# Sheet1.net
KiCad netlist of a schematic drawn in Altium Designer
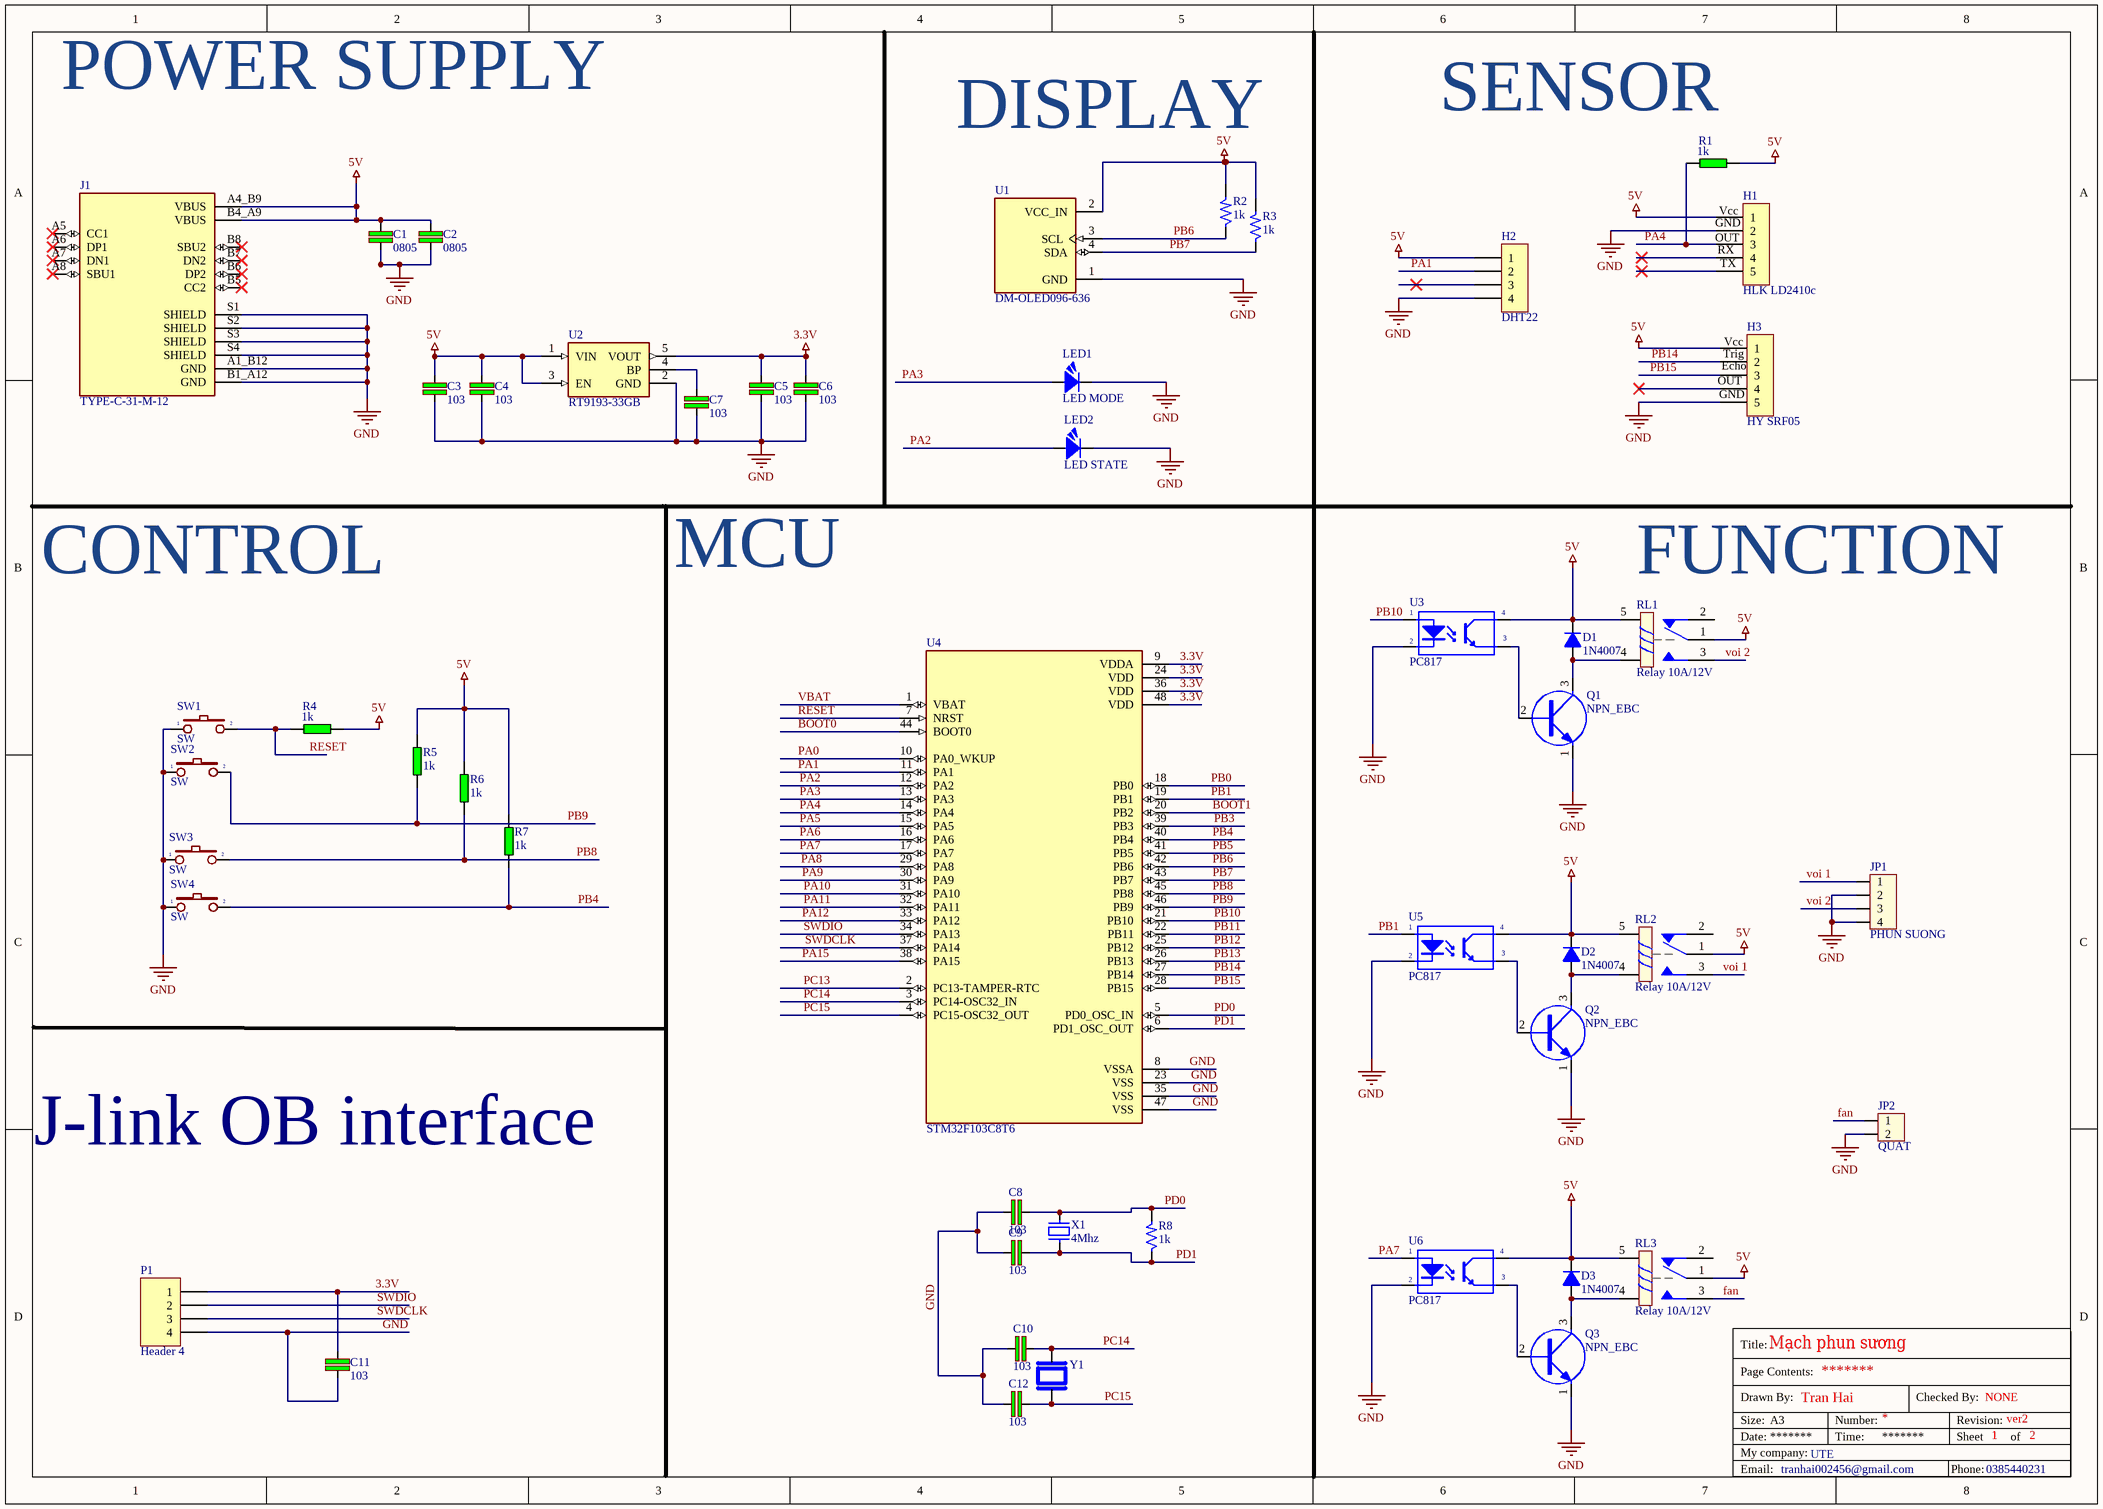
[diagram p0: Sheet1.SchDoc]

(export (version "E")
  (design (tool "Eeschema 10.0.6"))
  (components
    (comp (ref "C1")
      (value "0805")
      (footprint "C-0805")
      (description "Cap SMD")
      (libsource (lib "Library AL") (part "C"))
    )
    (comp (ref "C2")
      (value "0805")
      (footprint "C-0805")
      (description "Cap SMD")
      (libsource (lib "Library AL") (part "C"))
    )
    (comp (ref "C3")
      (value "103")
      (footprint "C-0805")
      (description "Cap SMD")
      (libsource (lib "Library AL") (part "C"))
    )
    (comp (ref "C4")
      (value "103")
      (footprint "C-0805")
      (description "Cap SMD")
      (libsource (lib "Library AL") (part "C"))
    )
    (comp (ref "C5")
      (value "103")
      (footprint "C-0805")
      (description "Cap SMD")
      (libsource (lib "Library AL") (part "C"))
    )
    (comp (ref "C6")
      (value "103")
      (footprint "C-0805")
      (description "Cap SMD")
      (libsource (lib "Library AL") (part "C"))
    )
    (comp (ref "C7")
      (value "103")
      (footprint "C-0805")
      (description "Cap SMD")
      (libsource (lib "Library AL") (part "C"))
    )
    (comp (ref "C8")
      (value "103")
      (footprint "C-0805")
      (description "Cap SMD")
      (libsource (lib "") (part "C_1"))
    )
    (comp (ref "C9")
      (value "103")
      (footprint "C-0805")
      (description "Cap SMD")
      (libsource (lib "") (part "C_1"))
    )
    (comp (ref "C10")
      (value "103")
      (footprint "C-0805")
      (description "Cap SMD")
      (libsource (lib "") (part "C_1"))
    )
    (comp (ref "C11")
      (value "103")
      (footprint "C-0805")
      (description "Cap SMD")
      (libsource (lib "Library AL") (part "C"))
    )
    (comp (ref "C12")
      (value "103")
      (footprint "C-0805")
      (description "Cap SMD")
      (libsource (lib "") (part "C_1"))
    )
    (comp (ref "D1")
      (value "1N4007")
      (footprint "D1A")
      (description "Diode 1A")
      (libsource (lib "Library AL") (part "D1A"))
    )
    (comp (ref "D2")
      (value "1N4007")
      (footprint "D1A")
      (description "Diode 1A")
      (libsource (lib "Library AL") (part "D1A"))
    )
    (comp (ref "D3")
      (value "1N4007")
      (footprint "D1A")
      (description "Diode 1A")
      (libsource (lib "Library AL") (part "D1A"))
    )
    (comp (ref "H1")
      (value "HLK LD2410c")
      (footprint "Header 5P DC 2.54")
      (description "Cắm")
      (libsource (lib "Altium_Lib_by_KhueNguyenCreator") (part "Header 5P 2.54 Duc Cong"))
    )
    (comp (ref "H2")
      (value "DHT22")
      (footprint "XH2.54M-4")
      (description "Cắm")
      (libsource (lib "Altium_Lib_by_KhueNguyenCreator") (part "Header 4P 2.54 Duc Thang"))
    )
    (comp (ref "H3")
      (value "HY SRF05")
      (footprint "XH2.54M-5")
      (description "Cắm")
      (libsource (lib "Altium_Lib_by_KhueNguyenCreator") (part "Header 5P 2.54 Duc Thang"))
    )
    (comp (ref "J1")
      (value "TYPE-C-31-M-12")
      (footprint "HRO_TYPE-C-31-M-12")
      (description "USB Connectors 24 Receptacle 1 8.94*7.3mm RoHS")
      (fields (field (name "MF") "HRO Electronics Co., Ltd."))
      (libsource (lib "TYPE-C-31-M-12") (part "TYPE-C-31-M-12"))
    )
    (comp (ref "JP1")
      (value "PHUN SUONG")
      (footprint "CON4")
      (description "Connector 4")
      (libsource (lib "Library AL") (part "Con4"))
    )
    (comp (ref "JP2")
      (value "QUAT")
      (footprint "CON2")
      (description "Connector 2")
      (libsource (lib "Library AL") (part "Con2"))
    )
    (comp (ref "LED1")
      (value "LED MODE")
      (footprint "LED-3")
      (description "LED Single colour Green and Red")
      (libsource (lib "Library AL") (part "LED_THU"))
    )
    (comp (ref "LED2")
      (value "LED STATE")
      (footprint "LED-3")
      (description "LED Single colour Green and Red")
      (libsource (lib "Library AL") (part "LED_THU"))
    )
    (comp (ref "P1")
      (value "Header 4")
      (footprint "HDR1X4")
      (description "Header, 4-Pin")
      (fields (field (name "PUBLISHER") "Altium Limited"))
      (libsource (lib "Library AL") (part "Header 4"))
    )
    (comp (ref "Q1")
      (value "NPN_EBC")
      (footprint "QTO-92")
      (description "NPN Transistor")
      (libsource (lib "Library AL") (part "NPN_EBC"))
    )
    (comp (ref "Q2")
      (value "NPN_EBC")
      (footprint "QTO-92")
      (description "NPN Transistor")
      (libsource (lib "Library AL") (part "NPN_EBC"))
    )
    (comp (ref "Q3")
      (value "NPN_EBC")
      (footprint "QTO-92")
      (description "NPN Transistor")
      (libsource (lib "Library AL") (part "NPN_EBC"))
    )
    (comp (ref "R1")
      (value "1k")
      (footprint "SM-1206")
      (description "Resistor 1/4W")
      (libsource (lib "") (part "RES_1"))
    )
    (comp (ref "R2")
      (value "1k")
      (footprint "SM-1206")
      (description "Resistor 1/4W")
      (libsource (lib "Library AL") (part "R"))
    )
    (comp (ref "R3")
      (value "1k")
      (footprint "SM-1206")
      (description "Resistor 1/4W")
      (libsource (lib "Library AL") (part "R"))
    )
    (comp (ref "R4")
      (value "1k")
      (footprint "SM-1206")
      (description "Resistor 1/4W")
      (libsource (lib "") (part "RES_1"))
    )
    (comp (ref "R5")
      (value "1k")
      (footprint "SM-1206")
      (description "Resistor 1/4W")
      (libsource (lib "Library AL") (part "RES"))
    )
    (comp (ref "R6")
      (value "1k")
      (footprint "SM-1206")
      (description "Resistor 1/4W")
      (libsource (lib "Library AL") (part "RES"))
    )
    (comp (ref "R7")
      (value "1k")
      (footprint "SM-1206")
      (description "Resistor 1/4W")
      (libsource (lib "Library AL") (part "RES"))
    )
    (comp (ref "R8")
      (value "1k")
      (footprint "SM-1206")
      (description "Resistor 1/4W")
      (libsource (lib "Library AL") (part "R"))
    )
    (comp (ref "RL1")
      (value "Relay 10A/12V")
      (footprint "RL_SPDT_10A")
      (description "Relay SPDT,10A - 12VDC 5 Pin")
      (libsource (lib "syhaunguyen") (part "Relay 1"))
    )
    (comp (ref "RL2")
      (value "Relay 10A/12V")
      (footprint "RL_SPDT_10A")
      (description "Relay SPDT,10A - 12VDC 5 Pin")
      (libsource (lib "syhaunguyen") (part "Relay 1"))
    )
    (comp (ref "RL3")
      (value "Relay 10A/12V")
      (footprint "RL_SPDT_10A")
      (description "Relay SPDT,10A - 12VDC 5 Pin")
      (libsource (lib "syhaunguyen") (part "Relay 1"))
    )
    (comp (ref "SW1")
      (value "SW")
      (footprint "SW2")
      (description "Switch button 2 pin")
      (libsource (lib "Library AL") (part "SW2"))
    )
    (comp (ref "SW2")
      (value "SW")
      (footprint "SW2")
      (description "Switch button 2 pin")
      (libsource (lib "Library AL") (part "SW2"))
    )
    (comp (ref "SW3")
      (value "SW")
      (footprint "SW2")
      (description "Switch button 2 pin")
      (libsource (lib "Library AL") (part "SW2"))
    )
    (comp (ref "SW4")
      (value "SW")
      (footprint "SW2")
      (description "Switch button 2 pin")
      (libsource (lib "Library AL") (part "SW2"))
    )
    (comp (ref "U1")
      (value "DM-OLED096-636")
      (footprint "MODULE_DM-OLED096-636")
      (description "0.96â€ 128 X 64 MONOCHROME GRAPHIC OLED DISPLAY MODULE - I2C")
      (fields (field (name "MF") "Display Module"))
      (libsource (lib "DM-OLED096-636") (part "DM-OLED096-636"))
    )
    (comp (ref "U2")
      (value "RT9193-33GB")
      (footprint "SOT94P279X129-5N")
      (description "Linear Voltage Regulator IC Positive Fixed 1 Output 300mA TSOT-23-5")
      (fields (field (name "MF") "Richtek USA") (field (name "DIGI-KEY_PART_NUMBER") "1028-1014-2-ND"))
      (libsource (lib "RT9193-33GB") (part "RT9193-33GB"))
    )
    (comp (ref "U3")
      (value "PC817")
      (footprint "DIP4/W0.3")
      (description "Single Opto")
      (libsource (lib "syhaunguyen") (part "PC817"))
    )
    (comp (ref "U4")
      (value "STM32F103C8T6")
      (footprint "QFP50P900X900X160-48N")
      (description "ARM® Cortex®-M3 STM32F1 Microcontroller IC 32-Bit 72MHz 64KB (64K x 8) FLASH 48-LQFP (7x7)")
      (fields (field (name "MF") "STMicroelectronics"))
      (libsource (lib "STM32F103C8T6") (part "STM32F103C8T6"))
    )
    (comp (ref "U5")
      (value "PC817")
      (footprint "DIP4/W0.3")
      (description "Single Opto")
      (libsource (lib "syhaunguyen") (part "PC817"))
    )
    (comp (ref "U6")
      (value "PC817")
      (footprint "DIP4/W0.3")
      (description "Single Opto")
      (libsource (lib "syhaunguyen") (part "PC817"))
    )
    (comp (ref "X1")
      (value "4Mhz")
      (footprint "XT2")
      (description "Crystal For all Crystal 2pin.")
      (libsource (lib "syhaunguyen") (part "XT2"))
    )
    (comp (ref "Y1")
      (value "ABS07-32.768KHZ-T")
      (footprint "XTAL_ABS07-32.768KHZ-T")
      (description "32.768 kHz Â±20ppm Crystal 12.5pF 70 kOhms 2-SMD, No Lead")
      (fields (field (name "MF") "Abracon"))
      (libsource (lib "ABS07-32.768KHZ-T") (part "ABS07-32.768KHZ-T"))
    )
  )
  (nets
    (net (code "1") (name "/BOOT0") (class "Default")
      (node (ref "U4") (pin "44") (pinfunction "BOOT0_44") (pintype "input"))
    )
    (net (code "2") (name "/BOOT1") (class "Default")
      (node (ref "U4") (pin "20") (pinfunction "PB2_20") (pintype "bidirectional"))
    )
    (net (code "3") (name "/PA0") (class "Default")
      (node (ref "U4") (pin "10") (pinfunction "PA0_WKUP_10") (pintype "bidirectional"))
    )
    (net (code "4") (name "/PA1") (class "Default")
      (node (ref "H2") (pin "2") (pinfunction "2_2") (pintype "passive"))
      (node (ref "U4") (pin "11") (pinfunction "PA1_11") (pintype "bidirectional"))
    )
    (net (code "5") (name "/PA2") (class "Default")
      (node (ref "LED2") (pin "1") (pinfunction "1_1") (pintype "passive"))
      (node (ref "U4") (pin "12") (pinfunction "PA2_12") (pintype "bidirectional"))
    )
    (net (code "6") (name "/PA3") (class "Default")
      (node (ref "LED1") (pin "1") (pinfunction "1_1") (pintype "passive"))
      (node (ref "U4") (pin "13") (pinfunction "PA3_13") (pintype "bidirectional"))
    )
    (net (code "7") (name "/PA4") (class "Default")
      (node (ref "H1") (pin "3") (pinfunction "3_3") (pintype "passive"))
      (node (ref "R1") (pin "1") (pinfunction "1_1") (pintype "passive"))
      (node (ref "U4") (pin "14") (pinfunction "PA4_14") (pintype "bidirectional"))
    )
    (net (code "8") (name "/PA5") (class "Default")
      (node (ref "U4") (pin "15") (pinfunction "PA5_15") (pintype "bidirectional"))
    )
    (net (code "9") (name "/PA6") (class "Default")
      (node (ref "U4") (pin "16") (pinfunction "PA6_16") (pintype "bidirectional"))
    )
    (net (code "10") (name "/PA7") (class "Default")
      (node (ref "U4") (pin "17") (pinfunction "PA7_17") (pintype "bidirectional"))
      (node (ref "U6") (pin "1") (pinfunction "A_1") (pintype "passive"))
    )
    (net (code "11") (name "/PA8") (class "Default")
      (node (ref "U4") (pin "29") (pinfunction "PA8_29") (pintype "bidirectional"))
    )
    (net (code "12") (name "/PA9") (class "Default")
      (node (ref "U4") (pin "30") (pinfunction "PA9_30") (pintype "bidirectional"))
    )
    (net (code "13") (name "/PA10") (class "Default")
      (node (ref "U4") (pin "31") (pinfunction "PA10_31") (pintype "bidirectional"))
    )
    (net (code "14") (name "/PA11") (class "Default")
      (node (ref "U4") (pin "32") (pinfunction "PA11_32") (pintype "bidirectional"))
    )
    (net (code "15") (name "/PA12") (class "Default")
      (node (ref "U4") (pin "33") (pinfunction "PA12_33") (pintype "bidirectional"))
    )
    (net (code "16") (name "/PA15") (class "Default")
      (node (ref "U4") (pin "38") (pinfunction "PA15_38") (pintype "bidirectional"))
    )
    (net (code "17") (name "/PB0") (class "Default")
      (node (ref "U4") (pin "18") (pinfunction "PB0_18") (pintype "bidirectional"))
    )
    (net (code "18") (name "/PB1") (class "Default")
      (node (ref "U4") (pin "19") (pinfunction "PB1_19") (pintype "bidirectional"))
      (node (ref "U5") (pin "1") (pinfunction "A_1") (pintype "passive"))
    )
    (net (code "19") (name "/PB3") (class "Default")
      (node (ref "U4") (pin "39") (pinfunction "PB3_39") (pintype "bidirectional"))
    )
    (net (code "20") (name "/PB4") (class "Default")
      (node (ref "R7") (pin "1") (pinfunction "1_1") (pintype "passive"))
      (node (ref "SW4") (pin "2") (pinfunction "2_2") (pintype "passive"))
      (node (ref "U4") (pin "40") (pinfunction "PB4_40") (pintype "bidirectional"))
    )
    (net (code "21") (name "/PB5") (class "Default")
      (node (ref "U4") (pin "41") (pinfunction "PB5_41") (pintype "bidirectional"))
    )
    (net (code "22") (name "/PB6") (class "Default")
      (node (ref "R2") (pin "1") (pinfunction "1_1") (pintype "passive"))
      (node (ref "U1") (pin "3") (pinfunction "SCL_3") (pintype "input"))
      (node (ref "U4") (pin "42") (pinfunction "PB6_42") (pintype "bidirectional"))
    )
    (net (code "23") (name "/PB7") (class "Default")
      (node (ref "R3") (pin "1") (pinfunction "1_1") (pintype "passive"))
      (node (ref "U1") (pin "4") (pinfunction "SDA_4") (pintype "bidirectional"))
      (node (ref "U4") (pin "43") (pinfunction "PB7_43") (pintype "bidirectional"))
    )
    (net (code "24") (name "/PB8") (class "Default")
      (node (ref "R6") (pin "1") (pinfunction "1_1") (pintype "passive"))
      (node (ref "SW3") (pin "2") (pinfunction "2_2") (pintype "passive"))
      (node (ref "U4") (pin "45") (pinfunction "PB8_45") (pintype "bidirectional"))
    )
    (net (code "25") (name "/PB9") (class "Default")
      (node (ref "R5") (pin "1") (pinfunction "1_1") (pintype "passive"))
      (node (ref "SW2") (pin "2") (pinfunction "2_2") (pintype "passive"))
      (node (ref "U4") (pin "46") (pinfunction "PB9_46") (pintype "bidirectional"))
    )
    (net (code "26") (name "/PB10") (class "Default")
      (node (ref "U3") (pin "1") (pinfunction "A_1") (pintype "passive"))
      (node (ref "U4") (pin "21") (pinfunction "PB10_21") (pintype "bidirectional"))
    )
    (net (code "27") (name "/PB11") (class "Default")
      (node (ref "U4") (pin "22") (pinfunction "PB11_22") (pintype "bidirectional"))
    )
    (net (code "28") (name "/PB12") (class "Default")
      (node (ref "U4") (pin "25") (pinfunction "PB12_25") (pintype "bidirectional"))
    )
    (net (code "29") (name "/PB13") (class "Default")
      (node (ref "U4") (pin "26") (pinfunction "PB13_26") (pintype "bidirectional"))
    )
    (net (code "30") (name "/PB14") (class "Default")
      (node (ref "H3") (pin "2") (pinfunction "2_2") (pintype "passive"))
      (node (ref "U4") (pin "27") (pinfunction "PB14_27") (pintype "bidirectional"))
    )
    (net (code "31") (name "/PB15") (class "Default")
      (node (ref "H3") (pin "3") (pinfunction "3_3") (pintype "passive"))
      (node (ref "U4") (pin "28") (pinfunction "PB15_28") (pintype "bidirectional"))
    )
    (net (code "32") (name "/PC13") (class "Default")
      (node (ref "U4") (pin "2") (pinfunction "PC13-TAMPER-RTC_2") (pintype "bidirectional"))
    )
    (net (code "33") (name "/PC14") (class "Default")
      (node (ref "C10") (pin "2") (pinfunction "2_2") (pintype "passive"))
      (node (ref "U4") (pin "3") (pinfunction "PC14-OSC32_IN_3") (pintype "bidirectional"))
      (node (ref "Y1") (pin "2") (pinfunction "2_2") (pintype "passive"))
    )
    (net (code "34") (name "/PC15") (class "Default")
      (node (ref "C12") (pin "2") (pinfunction "2_2") (pintype "passive"))
      (node (ref "U4") (pin "4") (pinfunction "PC15-OSC32_OUT_4") (pintype "bidirectional"))
      (node (ref "Y1") (pin "1") (pinfunction "1_1") (pintype "passive"))
    )
    (net (code "35") (name "/PD0") (class "Default")
      (node (ref "C8") (pin "2") (pinfunction "2_2") (pintype "passive"))
      (node (ref "R8") (pin "2") (pinfunction "2_2") (pintype "passive"))
      (node (ref "U4") (pin "5") (pinfunction "PD0_OSC_IN_5") (pintype "bidirectional"))
      (node (ref "X1") (pin "1") (pinfunction "1_1") (pintype "passive"))
    )
    (net (code "36") (name "/PD1") (class "Default")
      (node (ref "C9") (pin "2") (pinfunction "2_2") (pintype "passive"))
      (node (ref "R8") (pin "1") (pinfunction "1_1") (pintype "passive"))
      (node (ref "U4") (pin "6") (pinfunction "PD1_OSC_OUT_6") (pintype "bidirectional"))
      (node (ref "X1") (pin "2") (pinfunction "2_2") (pintype "passive"))
    )
    (net (code "37") (name "/RESET") (class "Default")
      (node (ref "R4") (pin "1") (pinfunction "1_1") (pintype "passive"))
      (node (ref "SW1") (pin "2") (pinfunction "2_2") (pintype "passive"))
      (node (ref "U4") (pin "7") (pinfunction "NRST_7") (pintype "input"))
    )
    (net (code "38") (name "/SWDCLK") (class "Default")
      (node (ref "P1") (pin "3") (pinfunction "3_3") (pintype "passive"))
      (node (ref "U4") (pin "37") (pinfunction "PA14_37") (pintype "bidirectional"))
    )
    (net (code "39") (name "/SWDIO") (class "Default")
      (node (ref "P1") (pin "2") (pinfunction "2_2") (pintype "passive"))
      (node (ref "U4") (pin "34") (pinfunction "PA13_34") (pintype "bidirectional"))
    )
    (net (code "40") (name "/VBAT") (class "Default")
      (node (ref "U4") (pin "1") (pinfunction "VBAT_1") (pintype "bidirectional"))
    )
    (net (code "41") (name "/fan") (class "Default")
      (node (ref "JP2") (pin "1") (pinfunction "1_1") (pintype "passive"))
      (node (ref "RL3") (pin "3") (pinfunction "3_3") (pintype "passive"))
    )
    (net (code "42") (name "/voi 1") (class "Default")
      (node (ref "JP1") (pin "1") (pinfunction "1_1") (pintype "passive"))
      (node (ref "RL2") (pin "3") (pinfunction "3_3") (pintype "passive"))
    )
    (net (code "43") (name "/voi 2") (class "Default")
      (node (ref "JP1") (pin "3") (pinfunction "3_3") (pintype "passive"))
      (node (ref "RL1") (pin "3") (pinfunction "3_3") (pintype "passive"))
    )
    (net (code "44") (name "3.3V") (class "Default")
      (node (ref "C11") (pin "2") (pinfunction "2_2") (pintype "passive"))
      (node (ref "C5") (pin "2") (pinfunction "2_2") (pintype "passive"))
      (node (ref "C6") (pin "2") (pinfunction "2_2") (pintype "passive"))
      (node (ref "P1") (pin "1") (pinfunction "1_1") (pintype "passive"))
      (node (ref "U2") (pin "5") (pinfunction "VOUT_5") (pintype "output"))
      (node (ref "U4") (pin "24") (pinfunction "VDD_24") (pintype "power_in"))
      (node (ref "U4") (pin "36") (pinfunction "VDD_36") (pintype "power_in"))
      (node (ref "U4") (pin "48") (pinfunction "VDD_48") (pintype "power_in"))
      (node (ref "U4") (pin "9") (pinfunction "VDDA_9") (pintype "power_in"))
    )
    (net (code "45") (name "5V") (class "Default")
      (node (ref "C1") (pin "2") (pinfunction "2_2") (pintype "passive"))
      (node (ref "C2") (pin "2") (pinfunction "2_2") (pintype "passive"))
      (node (ref "C3") (pin "2") (pinfunction "2_2") (pintype "passive"))
      (node (ref "C4") (pin "2") (pinfunction "2_2") (pintype "passive"))
      (node (ref "D1") (pin "2") (pinfunction "K_2") (pintype "passive"))
      (node (ref "D2") (pin "2") (pinfunction "K_2") (pintype "passive"))
      (node (ref "D3") (pin "2") (pinfunction "K_2") (pintype "passive"))
      (node (ref "H1") (pin "1") (pinfunction "1_1") (pintype "passive"))
      (node (ref "H2") (pin "1") (pinfunction "1_1") (pintype "passive"))
      (node (ref "H3") (pin "1") (pinfunction "1_1") (pintype "passive"))
      (node (ref "J1") (pin "A4_B9") (pinfunction "VBUS_A4_B9") (pintype "power_in"))
      (node (ref "J1") (pin "B4_A9") (pinfunction "VBUS_B4_A9") (pintype "power_in"))
      (node (ref "R1") (pin "2") (pinfunction "2_2") (pintype "passive"))
      (node (ref "R2") (pin "2") (pinfunction "2_2") (pintype "passive"))
      (node (ref "R3") (pin "2") (pinfunction "2_2") (pintype "passive"))
      (node (ref "R4") (pin "2") (pinfunction "2_2") (pintype "passive"))
      (node (ref "R5") (pin "2") (pinfunction "2_2") (pintype "passive"))
      (node (ref "R6") (pin "2") (pinfunction "2_2") (pintype "passive"))
      (node (ref "R7") (pin "2") (pinfunction "2_2") (pintype "passive"))
      (node (ref "RL1") (pin "1") (pinfunction "1_1") (pintype "passive"))
      (node (ref "RL1") (pin "5") (pinfunction "5_5") (pintype "passive"))
      (node (ref "RL2") (pin "1") (pinfunction "1_1") (pintype "passive"))
      (node (ref "RL2") (pin "5") (pinfunction "5_5") (pintype "passive"))
      (node (ref "RL3") (pin "1") (pinfunction "1_1") (pintype "passive"))
      (node (ref "RL3") (pin "5") (pinfunction "5_5") (pintype "passive"))
      (node (ref "U1") (pin "2") (pinfunction "VCC_IN_2") (pintype "power_in"))
      (node (ref "U2") (pin "1") (pinfunction "VIN_1") (pintype "input"))
      (node (ref "U2") (pin "3") (pinfunction "EN_3") (pintype "input"))
      (node (ref "U3") (pin "4") (pinfunction "C_4") (pintype "passive"))
      (node (ref "U5") (pin "4") (pinfunction "C_4") (pintype "passive"))
      (node (ref "U6") (pin "4") (pinfunction "C_4") (pintype "passive"))
    )
    (net (code "46") (name "GND") (class "Default")
      (node (ref "C1") (pin "1") (pinfunction "1_1") (pintype "passive"))
      (node (ref "C10") (pin "1") (pinfunction "1_1") (pintype "passive"))
      (node (ref "C11") (pin "1") (pinfunction "1_1") (pintype "passive"))
      (node (ref "C12") (pin "1") (pinfunction "1_1") (pintype "passive"))
      (node (ref "C2") (pin "1") (pinfunction "1_1") (pintype "passive"))
      (node (ref "C3") (pin "1") (pinfunction "1_1") (pintype "passive"))
      (node (ref "C4") (pin "1") (pinfunction "1_1") (pintype "passive"))
      (node (ref "C5") (pin "1") (pinfunction "1_1") (pintype "passive"))
      (node (ref "C6") (pin "1") (pinfunction "1_1") (pintype "passive"))
      (node (ref "C7") (pin "1") (pinfunction "1_1") (pintype "passive"))
      (node (ref "C8") (pin "1") (pinfunction "1_1") (pintype "passive"))
      (node (ref "C9") (pin "1") (pinfunction "1_1") (pintype "passive"))
      (node (ref "H1") (pin "2") (pinfunction "2_2") (pintype "passive"))
      (node (ref "H2") (pin "4") (pinfunction "4_4") (pintype "passive"))
      (node (ref "H3") (pin "5") (pinfunction "5_5") (pintype "passive"))
      (node (ref "J1") (pin "A1_B12") (pinfunction "GND_A1_B12") (pintype "power_in"))
      (node (ref "J1") (pin "B1_A12") (pinfunction "GND_B1_A12") (pintype "power_in"))
      (node (ref "J1") (pin "S1") (pinfunction "SHIELD_S1") (pintype "passive"))
      (node (ref "J1") (pin "S2") (pinfunction "SHIELD_S2") (pintype "passive"))
      (node (ref "J1") (pin "S3") (pinfunction "SHIELD_S3") (pintype "passive"))
      (node (ref "J1") (pin "S4") (pinfunction "SHIELD_S4") (pintype "passive"))
      (node (ref "JP1") (pin "2") (pinfunction "2_2") (pintype "passive"))
      (node (ref "JP1") (pin "4") (pinfunction "4_4") (pintype "passive"))
      (node (ref "JP2") (pin "2") (pinfunction "2_2") (pintype "passive"))
      (node (ref "LED1") (pin "2") (pinfunction "2_2") (pintype "passive"))
      (node (ref "LED2") (pin "2") (pinfunction "2_2") (pintype "passive"))
      (node (ref "P1") (pin "4") (pinfunction "4_4") (pintype "passive"))
      (node (ref "Q1") (pin "1") (pinfunction "E_1") (pintype "passive"))
      (node (ref "Q2") (pin "1") (pinfunction "E_1") (pintype "passive"))
      (node (ref "Q3") (pin "1") (pinfunction "E_1") (pintype "passive"))
      (node (ref "SW1") (pin "1") (pinfunction "1_1") (pintype "passive"))
      (node (ref "SW2") (pin "1") (pinfunction "1_1") (pintype "passive"))
      (node (ref "SW3") (pin "1") (pinfunction "1_1") (pintype "passive"))
      (node (ref "SW4") (pin "1") (pinfunction "1_1") (pintype "passive"))
      (node (ref "U1") (pin "1") (pinfunction "GND_1") (pintype "power_in"))
      (node (ref "U2") (pin "2") (pinfunction "GND_2") (pintype "power_in"))
      (node (ref "U3") (pin "2") (pinfunction "K_2") (pintype "passive"))
      (node (ref "U4") (pin "23") (pinfunction "VSS_23") (pintype "power_in"))
      (node (ref "U4") (pin "35") (pinfunction "VSS_35") (pintype "power_in"))
      (node (ref "U4") (pin "47") (pinfunction "VSS_47") (pintype "power_in"))
      (node (ref "U4") (pin "8") (pinfunction "VSSA_8") (pintype "power_in"))
      (node (ref "U5") (pin "2") (pinfunction "K_2") (pintype "passive"))
      (node (ref "U6") (pin "2") (pinfunction "K_2") (pintype "passive"))
    )
    (net (code "47") (name "Net-(D1-A)") (class "Default")
      (node (ref "D1") (pin "1") (pinfunction "A_1") (pintype "passive"))
      (node (ref "Q1") (pin "3") (pinfunction "C_3") (pintype "passive"))
      (node (ref "RL1") (pin "4") (pinfunction "4_4") (pintype "passive"))
    )
    (net (code "48") (name "Net-(D2-A)") (class "Default")
      (node (ref "D2") (pin "1") (pinfunction "A_1") (pintype "passive"))
      (node (ref "Q2") (pin "3") (pinfunction "C_3") (pintype "passive"))
      (node (ref "RL2") (pin "4") (pinfunction "4_4") (pintype "passive"))
    )
    (net (code "49") (name "Net-(D3-A)") (class "Default")
      (node (ref "D3") (pin "1") (pinfunction "A_1") (pintype "passive"))
      (node (ref "Q3") (pin "3") (pinfunction "C_3") (pintype "passive"))
      (node (ref "RL3") (pin "4") (pinfunction "4_4") (pintype "passive"))
    )
    (net (code "50") (name "Net-(Q1-B)") (class "Default")
      (node (ref "Q1") (pin "2") (pinfunction "B_2") (pintype "passive"))
      (node (ref "U3") (pin "3") (pinfunction "E_3") (pintype "passive"))
    )
    (net (code "51") (name "Net-(Q2-B)") (class "Default")
      (node (ref "Q2") (pin "2") (pinfunction "B_2") (pintype "passive"))
      (node (ref "U5") (pin "3") (pinfunction "E_3") (pintype "passive"))
    )
    (net (code "52") (name "Net-(Q3-B)") (class "Default")
      (node (ref "Q3") (pin "2") (pinfunction "B_2") (pintype "passive"))
      (node (ref "U6") (pin "3") (pinfunction "E_3") (pintype "passive"))
    )
    (net (code "53") (name "Net-(U2-BP)") (class "Default")
      (node (ref "C7") (pin "2") (pinfunction "2_2") (pintype "passive"))
      (node (ref "U2") (pin "4") (pinfunction "BP_4") (pintype "passive"))
    )
    (net (code "54") (name "unconnected-(H1-Pad4)") (class "Default")
      (node (ref "H1") (pin "4") (pinfunction "4_4") (pintype "passive"))
    )
    (net (code "55") (name "unconnected-(H1-Pad5)") (class "Default")
      (node (ref "H1") (pin "5") (pinfunction "5_5") (pintype "passive"))
    )
    (net (code "56") (name "unconnected-(H2-Pad3)") (class "Default")
      (node (ref "H2") (pin "3") (pinfunction "3_3") (pintype "passive"))
    )
    (net (code "57") (name "unconnected-(H3-Pad4)") (class "Default")
      (node (ref "H3") (pin "4") (pinfunction "4_4") (pintype "passive+no_connect"))
    )
    (net (code "58") (name "unconnected-(J1-CC1-PadA5)") (class "Default")
      (node (ref "J1") (pin "A5") (pinfunction "CC1_A5") (pintype "bidirectional+no_connect"))
    )
    (net (code "59") (name "unconnected-(J1-CC2-PadB5)") (class "Default")
      (node (ref "J1") (pin "B5") (pinfunction "CC2_B5") (pintype "bidirectional+no_connect"))
    )
    (net (code "60") (name "unconnected-(J1-DN1-PadA7)") (class "Default")
      (node (ref "J1") (pin "A7") (pinfunction "DN1_A7") (pintype "bidirectional+no_connect"))
    )
    (net (code "61") (name "unconnected-(J1-DN2-PadB7)") (class "Default")
      (node (ref "J1") (pin "B7") (pinfunction "DN2_B7") (pintype "bidirectional+no_connect"))
    )
    (net (code "62") (name "unconnected-(J1-DP1-PadA6)") (class "Default")
      (node (ref "J1") (pin "A6") (pinfunction "DP1_A6") (pintype "bidirectional+no_connect"))
    )
    (net (code "63") (name "unconnected-(J1-DP2-PadB6)") (class "Default")
      (node (ref "J1") (pin "B6") (pinfunction "DP2_B6") (pintype "bidirectional+no_connect"))
    )
    (net (code "64") (name "unconnected-(J1-SBU1-PadA8)") (class "Default")
      (node (ref "J1") (pin "A8") (pinfunction "SBU1_A8") (pintype "bidirectional+no_connect"))
    )
    (net (code "65") (name "unconnected-(J1-SBU2-PadB8)") (class "Default")
      (node (ref "J1") (pin "B8") (pinfunction "SBU2_B8") (pintype "bidirectional+no_connect"))
    )
    (net (code "66") (name "unconnected-(RL1-Pad2)") (class "Default")
      (node (ref "RL1") (pin "2") (pinfunction "2_2") (pintype "passive"))
    )
    (net (code "67") (name "unconnected-(RL2-Pad2)") (class "Default")
      (node (ref "RL2") (pin "2") (pinfunction "2_2") (pintype "passive"))
    )
    (net (code "68") (name "unconnected-(RL3-Pad2)") (class "Default")
      (node (ref "RL3") (pin "2") (pinfunction "2_2") (pintype "passive"))
    )
  )
)
